# Triggers.net
KiCad netlist of a schematic drawn in Altium Designer
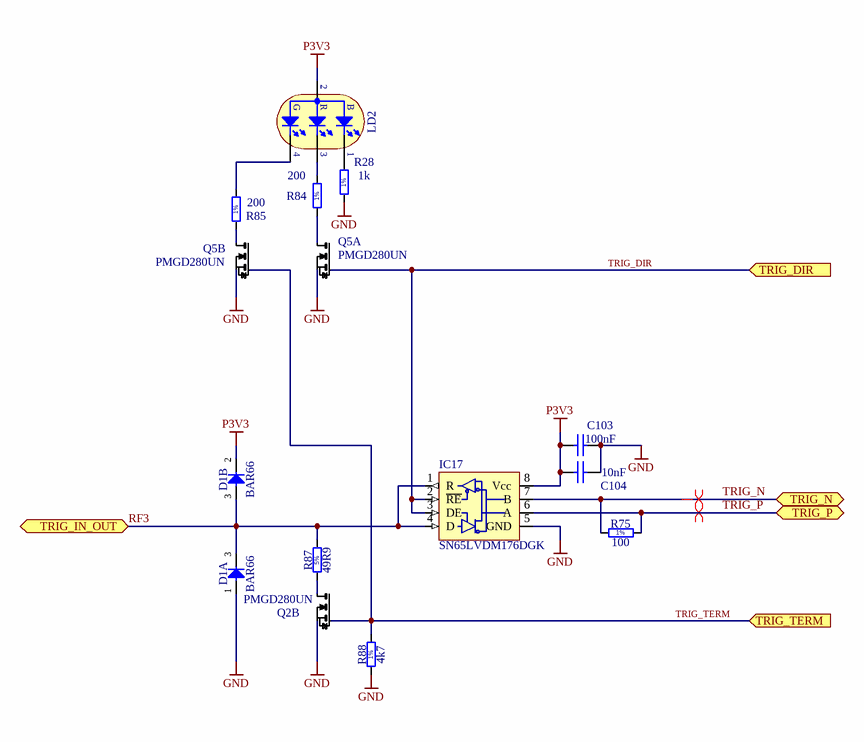
[diagram p0: Triggers.SchDoc]

(export (version "E")
  (design (tool "Eeschema 10.0.6"))
  (components
    (comp (ref "C103")
      (value "100nF")
      (footprint "CAPC0603X33N")
      (description "Non-polarised capacitor")
      (fields
        (field (name "PART NUMBER") "CC0201_100NF_6.3V_10%_X5R")
        (field (name "VOLTAGE") "6.3V")
        (field (name "AUTHOR") "CERN DEM JLC")
      )
      (libsource (lib "Capacitors") (part "Capacitor - non polarized"))
    )
    (comp (ref "C104")
      (value "10nF")
      (footprint "CAPC0603X33N")
      (description "Non-polarised capacitor")
      (fields
        (field (name "PART NUMBER") "CC0201_10NF_10V_10%_X5R")
        (field (name "VOLTAGE") "10V")
        (field (name "AUTHOR") "CERN DEM JLC")
      )
      (libsource (lib "Capacitors") (part "Capacitor - non polarized"))
    )
    (comp (ref "D1")
      (value "BAR66")
      (footprint "SOT95P240X110-3N")
      (description "Serial Diode")
      (fields
        (field (name "VOLTAGE") "150V")
        (field (name "POWER") "250mA")
        (field (name "AUTHOR") "CERN DEM JLC")
      )
      (libsource (lib "ICs And Semiconductors") (part "Diode x2 A1C3_A3C2"))
    )
    (comp (ref "IC17")
      (value "SN65LVDM176DGK")
      (footprint "MSOP8 TI/AD")
      (description "High Speed Differential Transceiver LVDS/LVTTL")
      (libsource (lib "Buffers & Drivers") (part "SN65LVDM176"))
    )
    (comp (ref "LD2")
      (value "Blue/Red/Green")
      (footprint "LED_AVAGO_HSMF-C113")
      (description "Tricolor LEDs 1 Cathode Blue, 2 Common Anode, 3 Cathode Red, 4 Cathode Green")
      (fields
        (field (name "PART NUMBER") "LED_AVAGO_HSMF-C113")
        (field (name "MANUFACTURER") "AVAGO TECHNOLOGIES")
        (field (name "AUTHOR") "CERN DEM JLC")
      )
      (libsource (lib "ICs And Semiconductors") (part "LED Blue-Red-Green 1CB_2AC_3CR_4CG"))
    )
    (comp (ref "Q2")
      (value "PMGD280UN")
      (footprint "SOT-363")
      (description "Dual NMOS 20V,08.A, 340mR, Vt=0.7V")
      (libsource (lib "LIBRARY_SCH") (part "Q_PMGD280UN"))
    )
    (comp (ref "Q5")
      (value "PMGD280UN")
      (footprint "SOT-363")
      (description "Dual NMOS 20V,08.A, 340mR, Vt=0.7V")
      (libsource (lib "LIBRARY_SCH") (part "Q_PMGD280UN"))
    )
    (comp (ref "R28")
      (value "1k")
      (footprint "RESC1005X40N")
      (description "Resistor - 1%")
      (fields
        (field (name "PART NUMBER") "R0402_1K_1%_0.0625W_100PPM")
        (field (name "POWER") "0.0625W")
        (field (name "AUTHOR") "CERN DEM JLC")
      )
      (libsource (lib "Resistors") (part "Resistor - 1%"))
    )
    (comp (ref "R75")
      (value "100")
      (footprint "RESC1005X40N")
      (description "Resistor - 1%")
      (fields
        (field (name "PART NUMBER") "R0402_100R_1%_0.0625W_100PPM")
        (field (name "POWER") "0.0625W")
        (field (name "AUTHOR") "CERN DEM JLC")
      )
      (libsource (lib "Resistors") (part "Resistor - 1%"))
    )
    (comp (ref "R84")
      (value "200")
      (footprint "RESC1005X40N")
      (description "Resistor - 1%")
      (fields
        (field (name "PART NUMBER") "R0402_200R_1%_0.0625W_100PPM")
        (field (name "POWER") "0.0625W")
        (field (name "AUTHOR") "CERN DEM JLC")
      )
      (libsource (lib "Resistors") (part "Resistor - 1%"))
    )
    (comp (ref "R85")
      (value "200")
      (footprint "RESC1005X40N")
      (description "Resistor - 1%")
      (fields
        (field (name "PART NUMBER") "R0402_200R_1%_0.0625W_100PPM")
        (field (name "POWER") "0.0625W")
        (field (name "AUTHOR") "CERN DEM JLC")
      )
      (libsource (lib "Resistors") (part "Resistor - 1%"))
    )
    (comp (ref "R87")
      (value "49R9")
      (footprint "RESC3225X70N")
      (description "Resistor - 5%")
      (fields
        (field (name "PART NUMBER") "R1210_49R9_1%_0.33W_100PPM")
        (field (name "POWER") "0.33W")
        (field (name "AUTHOR") "CERN DEM JLC")
      )
      (libsource (lib "Resistors") (part "Resistor - 5%"))
    )
    (comp (ref "R88")
      (value "4k7")
      (footprint "RESC1005X40N")
      (description "Resistor - 1%")
      (fields
        (field (name "PART NUMBER") "R0402_4K7_1%_0.0625W_100PPM")
        (field (name "POWER") "0.0625W")
        (field (name "AUTHOR") "CERN DEM JLC")
      )
      (libsource (lib "Resistors") (part "Resistor - 1%"))
    )
  )
  (nets
    (net (code "1") (name "/RF3") (class "Default")
      (node (ref "D1") (pin "3") (pinfunction "COMAC_3") (pintype "passive"))
      (node (ref "IC17") (pin "1") (pinfunction "R_1") (pintype "output"))
      (node (ref "IC17") (pin "4") (pinfunction "D_4") (pintype "input"))
      (node (ref "R87") (pin "2") (pinfunction "2_2") (pintype "passive"))
    )
    (net (code "2") (name "/TRIG_DIR") (class "Default")
      (node (ref "IC17") (pin "2") (pinfunction "~{RE}_2") (pintype "input"))
      (node (ref "IC17") (pin "3") (pinfunction "DE_3") (pintype "input"))
      (node (ref "Q5") (pin "2") (pinfunction "G1_2") (pintype "input"))
    )
    (net (code "3") (name "/TRIG_N") (class "Default")
      (node (ref "IC17") (pin "7") (pinfunction "B_7") (pintype "bidirectional"))
      (node (ref "R75") (pin "1") (pinfunction "1_1") (pintype "passive"))
    )
    (net (code "4") (name "/TRIG_P") (class "Default")
      (node (ref "IC17") (pin "6") (pinfunction "A_6") (pintype "bidirectional"))
      (node (ref "R75") (pin "2") (pinfunction "2_2") (pintype "passive"))
    )
    (net (code "5") (name "/TRIG_TERM") (class "Default")
      (node (ref "Q2") (pin "5") (pinfunction "G1_5") (pintype "input"))
      (node (ref "Q5") (pin "5") (pinfunction "G1_5") (pintype "input"))
      (node (ref "R88") (pin "2") (pinfunction "2_2") (pintype "passive"))
    )
    (net (code "6") (name "GND") (class "Default")
      (node (ref "C103") (pin "2") (pinfunction "2_2") (pintype "passive"))
      (node (ref "C104") (pin "2") (pinfunction "2_2") (pintype "passive"))
      (node (ref "D1") (pin "1") (pinfunction "A_1") (pintype "passive"))
      (node (ref "IC17") (pin "5") (pinfunction "GND_5") (pintype "power_in"))
      (node (ref "Q2") (pin "4") (pinfunction "S1_4") (pintype "open_emitter"))
      (node (ref "Q5") (pin "1") (pinfunction "S1_1") (pintype "open_emitter"))
      (node (ref "Q5") (pin "4") (pinfunction "S1_4") (pintype "open_emitter"))
      (node (ref "R28") (pin "1") (pinfunction "1_1") (pintype "passive"))
      (node (ref "R88") (pin "1") (pinfunction "1_1") (pintype "passive"))
    )
    (net (code "7") (name "Net-(LD2-CB)") (class "Default")
      (node (ref "LD2") (pin "1") (pinfunction "CB_1") (pintype "passive"))
      (node (ref "R28") (pin "2") (pinfunction "2_2") (pintype "passive"))
    )
    (net (code "8") (name "Net-(LD2-CG)") (class "Default")
      (node (ref "LD2") (pin "4") (pinfunction "CG_4") (pintype "passive"))
      (node (ref "R85") (pin "2") (pinfunction "2_2") (pintype "passive"))
    )
    (net (code "9") (name "Net-(LD2-CR)") (class "Default")
      (node (ref "LD2") (pin "3") (pinfunction "CR_3") (pintype "passive"))
      (node (ref "R84") (pin "2") (pinfunction "2_2") (pintype "passive"))
    )
    (net (code "10") (name "Net-(Q2B-D1)") (class "Default")
      (node (ref "Q2") (pin "6") (pinfunction "D1_6") (pintype "open_collector"))
      (node (ref "R87") (pin "1") (pinfunction "1_1") (pintype "passive"))
    )
    (net (code "11") (name "Net-(Q5A-D1)") (class "Default")
      (node (ref "Q5") (pin "3") (pinfunction "D1_3") (pintype "open_collector"))
      (node (ref "R84") (pin "1") (pinfunction "1_1") (pintype "passive"))
    )
    (net (code "12") (name "Net-(Q5B-D1)") (class "Default")
      (node (ref "Q5") (pin "6") (pinfunction "D1_6") (pintype "open_collector"))
      (node (ref "R85") (pin "1") (pinfunction "1_1") (pintype "passive"))
    )
    (net (code "13") (name "P3V3") (class "Default")
      (node (ref "C103") (pin "1") (pinfunction "1_1") (pintype "passive"))
      (node (ref "C104") (pin "1") (pinfunction "1_1") (pintype "passive"))
      (node (ref "D1") (pin "2") (pinfunction "C_2") (pintype "passive"))
      (node (ref "IC17") (pin "8") (pinfunction "Vcc_8") (pintype "power_in"))
      (node (ref "LD2") (pin "2") (pinfunction "AC_2") (pintype "passive"))
    )
  )
)
